# boost_stage.net
KiCad netlist of a schematic drawn in Altium Designer
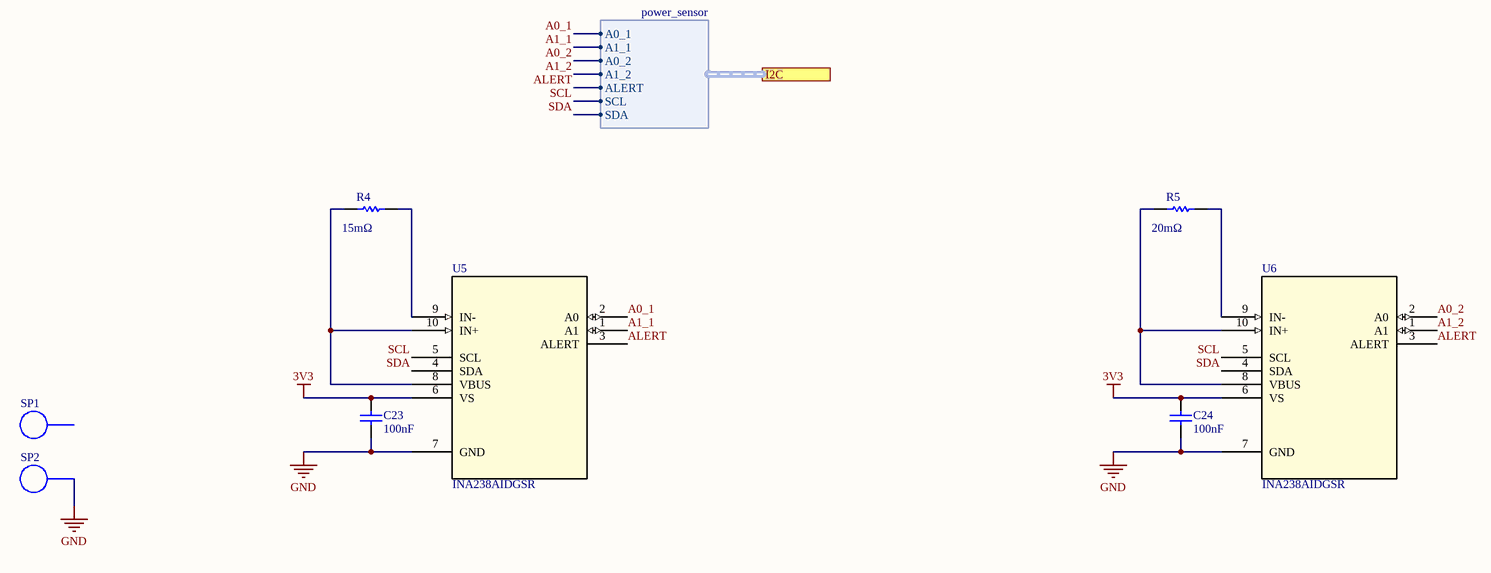
[diagram p0: boost_stage.SchDoc]

(export (version "E")
  (design (tool "Eeschema 10.0.6"))
  (components
    (comp (ref "C23")
      (value "100nF")
      (footprint "C0603")
      (description "25V 100nF X7R ±10% 0603 Multilayer Ceramic Capacitors MLCC - SMD/SMT ROHS")
      (fields (field (name "TOLERANCE") "10%") (field (name "VOLTAGE") "25V"))
      (libsource (lib "Sunswift Racing") (part "Capacitor"))
    )
    (comp (ref "C24")
      (value "100nF")
      (footprint "C0603")
      (description "25V 100nF X7R ±10% 0603 Multilayer Ceramic Capacitors MLCC - SMD/SMT ROHS")
      (fields (field (name "TOLERANCE") "10%") (field (name "VOLTAGE") "25V"))
      (libsource (lib "Sunswift Racing") (part "Capacitor"))
    )
    (comp (ref "R4")
      (value "15mΩ")
      (footprint "FP-PA2512E-R007-0R10-MFG")
      (description "Fixed Resistor, 3W, 0.015ohm, 0.2121V, 1% +/-Tol, 50ppm/Cel, Surface Mount, 2512")
      (fields (field (name "TOLERANCE") "1%") (field (name "Comment") "PA2512FKE7T0R015E"))
      (libsource (lib "Sunswift Racing") (part "1029c3af85768c4190bb7ad29bc67b5"))
    )
    (comp (ref "R5")
      (value "20mΩ")
      (footprint "FP-PA2512E-R007-0R10-MFG")
      (description "Current Sensor-Low TCR Chip Resistor Automotive Grade Metal Film 2512 20mOhm 1% Emboss T/R")
      (fields (field (name "TOLERANCE") "1%") (field (name "Comment") "PA2512FKF7W0R02E"))
      (libsource (lib "Sunswift Racing") (part "1029c3af85768c4190bb7ad29bc67b5"))
    )
    (comp (ref "SP1")
      (value "Solder Pad")
      (footprint "Solder Pad-Footprint-1")
      (description "64mm^2 solder pad for wire to board connections,")
      (libsource (lib "Sunswift Racing") (part "Solder Pad-Symbol-1"))
    )
    (comp (ref "SP2")
      (value "Solder Pad")
      (footprint "Solder Pad-Footprint-1")
      (description "64mm^2 solder pad for wire to board connections,")
      (libsource (lib "Sunswift Racing") (part "Solder Pad-Symbol-1"))
    )
    (comp (ref "U5")
      (value "INA238AIDGSR")
      (footprint "VSSOP_8AIDGST_TEX")
      (fields (field (name "COPYRIGHT") "Copyright (C) 2026 Ultra Librarian. All rights reserved."))
      (libsource (lib "Sunswift Racing") (part "INA238AIDGSR"))
    )
    (comp (ref "U6")
      (value "INA238AIDGSR")
      (footprint "VSSOP_8AIDGST_TEX")
      (fields (field (name "COPYRIGHT") "Copyright (C) 2026 Ultra Librarian. All rights reserved."))
      (libsource (lib "Sunswift Racing") (part "INA238AIDGSR"))
    )
  )
  (nets
    (net (code "2") (name "/A0_1") (class "Default")
      (node (ref "U5") (pin "2") (pinfunction "A0_2") (pintype "bidirectional"))
    )
    (net (code "3") (name "/A0_2") (class "Default")
      (node (ref "U6") (pin "2") (pinfunction "A0_2") (pintype "bidirectional"))
    )
    (net (code "4") (name "/A1_1") (class "Default")
      (node (ref "U5") (pin "1") (pinfunction "A1_1") (pintype "bidirectional"))
    )
    (net (code "5") (name "/A1_2") (class "Default")
      (node (ref "U6") (pin "1") (pinfunction "A1_1") (pintype "bidirectional"))
    )
    (net (code "6") (name "/ALERT") (class "Default")
      (node (ref "U5") (pin "3") (pinfunction "ALERT_3") (pintype "passive"))
      (node (ref "U6") (pin "3") (pinfunction "ALERT_3") (pintype "passive"))
    )
    (net (code "7") (name "/SCL") (class "Default")
      (node (ref "U5") (pin "5") (pinfunction "SCL_5") (pintype "passive"))
      (node (ref "U6") (pin "5") (pinfunction "SCL_5") (pintype "passive"))
    )
    (net (code "8") (name "/SDA") (class "Default")
      (node (ref "U5") (pin "4") (pinfunction "SDA_4") (pintype "passive"))
      (node (ref "U6") (pin "4") (pinfunction "SDA_4") (pintype "passive"))
    )
    (net (code "10") (name "3V3") (class "Default")
      (node (ref "C23") (pin "2") (pinfunction "2_2") (pintype "passive"))
      (node (ref "C24") (pin "2") (pinfunction "2_2") (pintype "passive"))
      (node (ref "U5") (pin "6") (pinfunction "VS_6") (pintype "passive"))
      (node (ref "U6") (pin "6") (pinfunction "VS_6") (pintype "passive"))
    )
    (net (code "11") (name "GND") (class "Default")
      (node (ref "C23") (pin "1") (pinfunction "1_1") (pintype "passive"))
      (node (ref "C24") (pin "1") (pinfunction "1_1") (pintype "passive"))
      (node (ref "SP2") (pin "SP") (pinfunction "Solder_Pad_SP") (pintype "passive"))
      (node (ref "U5") (pin "7") (pinfunction "GND_7") (pintype "power_in"))
      (node (ref "U6") (pin "7") (pinfunction "GND_7") (pintype "power_in"))
    )
    (net (code "12") (name "Net-(U5-IN+)") (class "Default")
      (node (ref "R4") (pin "1") (pinfunction "1_1") (pintype "passive"))
      (node (ref "U5") (pin "10") (pinfunction "IN+_10") (pintype "input"))
      (node (ref "U5") (pin "8") (pinfunction "VBUS_8") (pintype "passive"))
    )
    (net (code "13") (name "Net-(U5-IN-)") (class "Default")
      (node (ref "R4") (pin "2") (pinfunction "2_2") (pintype "passive"))
      (node (ref "U5") (pin "9") (pinfunction "IN-_9") (pintype "input"))
    )
    (net (code "14") (name "Net-(U6-IN+)") (class "Default")
      (node (ref "R5") (pin "1") (pinfunction "1_1") (pintype "passive"))
      (node (ref "U6") (pin "10") (pinfunction "IN+_10") (pintype "input"))
      (node (ref "U6") (pin "8") (pinfunction "VBUS_8") (pintype "passive"))
    )
    (net (code "15") (name "Net-(U6-IN-)") (class "Default")
      (node (ref "R5") (pin "2") (pinfunction "2_2") (pintype "passive"))
      (node (ref "U6") (pin "9") (pinfunction "IN-_9") (pintype "input"))
    )
    (net (code "16") (name "unconnected-(SP1-Solder_Pad-PadSP)") (class "Default")
      (node (ref "SP1") (pin "SP") (pinfunction "Solder_Pad_SP") (pintype "passive"))
    )
  )
)
